# CAN.net
KiCad netlist of a schematic drawn in EAGLE
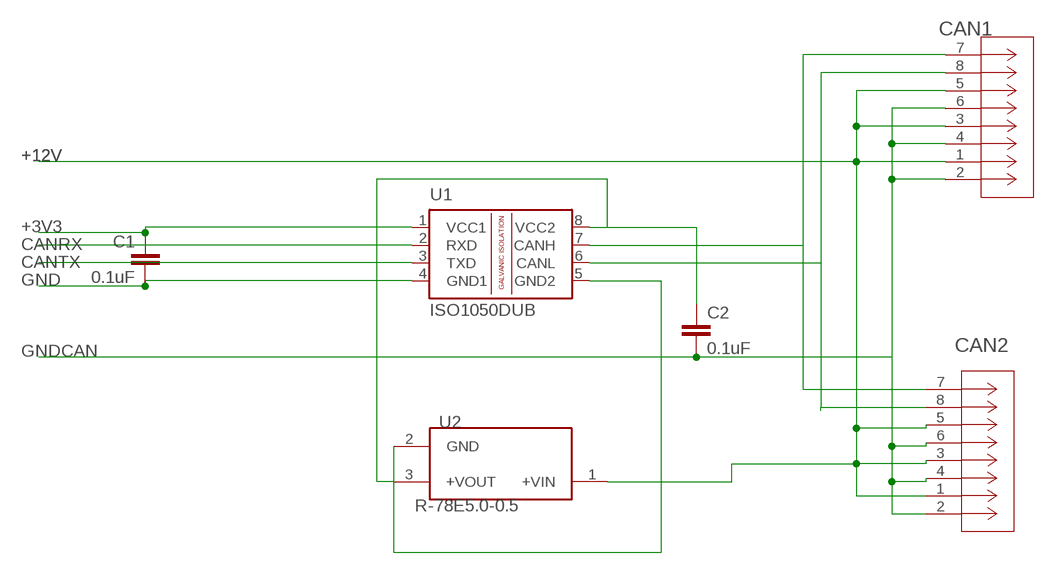
[diagram p0: schematic, sheet 1]

(export (version "E")
  (design (tool "Eeschema 10.0.6"))
  (components
    (comp (ref "C1")
      (value "0.1uF")
      (footprint "eagle-import:C5B3.5")
      (libsource (lib "eagle-import") (part "C5/3.5"))
    )
    (comp (ref "C2")
      (value "0.1uF")
      (footprint "eagle-import:C2.5-4")
      (libsource (lib "eagle-import") (part "C2.5/4"))
    )
    (comp (ref "CAN1")
      (value "A-2004-2-4-LPS-N-R")
      (footprint "eagle-import:CONN_4-LPS-N-R_ASM")
      (fields (field (name "COPYRIGHT") "Copyright (C) 2021 Ultra Librarian. All rights reserved."))
      (libsource (lib "eagle-import") (part "A-2004-2-4-LPS-N-R"))
    )
    (comp (ref "CAN2")
      (value "A-2004-2-4-LPS-N-R")
      (footprint "eagle-import:CONN_4-LPS-N-R_ASM")
      (fields (field (name "COPYRIGHT") "Copyright (C) 2021 Ultra Librarian. All rights reserved."))
      (libsource (lib "eagle-import") (part "A-2004-2-4-LPS-N-R"))
    )
    (comp (ref "U1")
      (value "ISO1050DUB")
      (footprint "eagle-import:DUB-R-PDSO-G8")
      (fields (field (name "MPN") "ISO1050DUBR"))
      (libsource (lib "eagle-import") (part "ISO1050DUB"))
    )
    (comp (ref "U2")
      (value "R-78E5.0-0.5")
      (footprint "eagle-import:CONV_R-78E5.0-0.5")
      (fields (field (name "DIGI-KEY_PART_NUMBER") "945-1648-5-ND") (field (name "MF") "Recom Power"))
      (libsource (lib "eagle-import") (part "R-78E5.0-0.5"))
    )
  )
  (nets
    (net (code "1") (name "/+3V3") (class "Default")
      (node (ref "C1") (pin "2") (pinfunction "2_2") (pintype "passive"))
      (node (ref "U1") (pin "1") (pinfunction "VCC1_1") (pintype "input"))
    )
    (net (code "2") (name "/+12V") (class "Default")
      (node (ref "CAN1") (pin "1") (pinfunction "1_1") (pintype "passive"))
      (node (ref "CAN1") (pin "3") (pinfunction "3_3") (pintype "passive"))
      (node (ref "CAN1") (pin "5") (pinfunction "5_5") (pintype "passive"))
      (node (ref "CAN2") (pin "1") (pinfunction "1_1") (pintype "passive"))
      (node (ref "CAN2") (pin "3") (pinfunction "3_3") (pintype "passive"))
      (node (ref "CAN2") (pin "5") (pinfunction "5_5") (pintype "passive"))
      (node (ref "U2") (pin "1") (pinfunction "+VIN_1") (pintype "input"))
    )
    (net (code "3") (name "/CANRX") (class "Default")
      (node (ref "U1") (pin "2") (pinfunction "RXD_2") (pintype "input"))
    )
    (net (code "4") (name "/CANTX") (class "Default")
      (node (ref "U1") (pin "3") (pinfunction "TXD_3") (pintype "input"))
    )
    (net (code "5") (name "/GND") (class "Default")
      (node (ref "C1") (pin "1") (pinfunction "1_1") (pintype "passive"))
      (node (ref "U1") (pin "4") (pinfunction "GND1_4") (pintype "input"))
    )
    (net (code "6") (name "/GNDCAN") (class "Default")
      (node (ref "C2") (pin "2") (pinfunction "2_2") (pintype "passive"))
      (node (ref "CAN1") (pin "2") (pinfunction "2_2") (pintype "passive"))
      (node (ref "CAN1") (pin "4") (pinfunction "4_4") (pintype "passive"))
      (node (ref "CAN1") (pin "6") (pinfunction "6_6") (pintype "passive"))
      (node (ref "CAN2") (pin "2") (pinfunction "2_2") (pintype "passive"))
      (node (ref "CAN2") (pin "4") (pinfunction "4_4") (pintype "passive"))
      (node (ref "CAN2") (pin "6") (pinfunction "6_6") (pintype "passive"))
    )
    (net (code "7") (name "Net-(U1-CANH)") (class "Default")
      (node (ref "CAN1") (pin "7") (pinfunction "7_7") (pintype "passive"))
      (node (ref "CAN2") (pin "7") (pinfunction "7_7") (pintype "passive"))
      (node (ref "U1") (pin "7") (pinfunction "CANH_7") (pintype "input"))
    )
    (net (code "8") (name "Net-(U1-CANL)") (class "Default")
      (node (ref "CAN1") (pin "8") (pinfunction "8_8") (pintype "passive"))
      (node (ref "CAN2") (pin "8") (pinfunction "8_8") (pintype "passive"))
      (node (ref "U1") (pin "6") (pinfunction "CANL_6") (pintype "input"))
    )
    (net (code "9") (name "Net-(U1-GND2)") (class "Default")
      (node (ref "U1") (pin "5") (pinfunction "GND2_5") (pintype "input"))
      (node (ref "U2") (pin "2") (pinfunction "GND_2") (pintype "power_in"))
    )
    (net (code "10") (name "Net-(U1-VCC2)") (class "Default")
      (node (ref "C2") (pin "1") (pinfunction "1_1") (pintype "passive"))
      (node (ref "U1") (pin "8") (pinfunction "VCC2_8") (pintype "input"))
    )
    (net (code "11") (name "unconnected-(U2-+VOUT-Pad3)") (class "Default")
      (node (ref "U2") (pin "3") (pinfunction "+VOUT_3") (pintype "output"))
    )
  )
)
